# ShiftRegister.net
KiCad netlist of a schematic drawn in Altium Designer
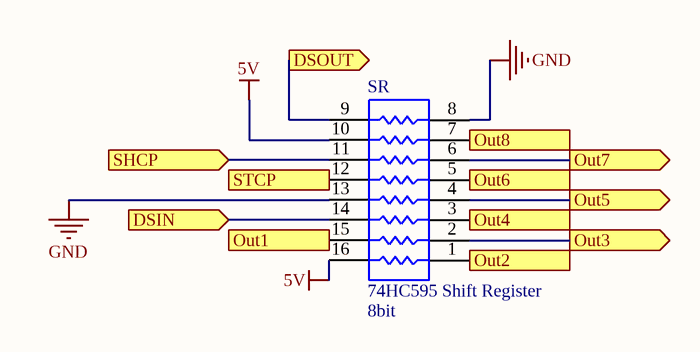
[diagram p0: ShiftRegister.SchDoc]

(export (version "E")
  (design (tool "Eeschema 10.0.6"))
  (components
    (comp (ref "SR")
      (value "74HC595 Shift Register")
      (footprint "SO-16_L")
      (description "Isolated Resistor Network")
      (fields (field (name "ALTIUM_VALUE") "8bit") (field (name "PUBLISHER") "Altium Limited"))
      (libsource (lib "Miscellaneous Devices") (part "Res Pack3"))
    )
  )
  (nets
    (net (code "1") (name "/DSIN") (class "Default")
      (node (ref "SR") (pin "14") (pinfunction "14_14") (pintype "passive"))
    )
    (net (code "2") (name "/DSOUT") (class "Default")
      (node (ref "SR") (pin "9") (pinfunction "9_9") (pintype "passive"))
    )
    (net (code "3") (name "/Out1") (class "Default")
      (node (ref "SR") (pin "15") (pinfunction "15_15") (pintype "passive"))
    )
    (net (code "4") (name "/Out2") (class "Default")
      (node (ref "SR") (pin "1") (pinfunction "1_1") (pintype "passive"))
    )
    (net (code "5") (name "/Out3") (class "Default")
      (node (ref "SR") (pin "2") (pinfunction "2_2") (pintype "passive"))
    )
    (net (code "6") (name "/Out4") (class "Default")
      (node (ref "SR") (pin "3") (pinfunction "3_3") (pintype "passive"))
    )
    (net (code "7") (name "/Out5") (class "Default")
      (node (ref "SR") (pin "4") (pinfunction "4_4") (pintype "passive"))
    )
    (net (code "8") (name "/Out6") (class "Default")
      (node (ref "SR") (pin "5") (pinfunction "5_5") (pintype "passive"))
    )
    (net (code "9") (name "/Out7") (class "Default")
      (node (ref "SR") (pin "6") (pinfunction "6_6") (pintype "passive"))
    )
    (net (code "10") (name "/Out8") (class "Default")
      (node (ref "SR") (pin "7") (pinfunction "7_7") (pintype "passive"))
    )
    (net (code "11") (name "/SHCP") (class "Default")
      (node (ref "SR") (pin "11") (pinfunction "11_11") (pintype "passive"))
    )
    (net (code "12") (name "/STCP") (class "Default")
      (node (ref "SR") (pin "12") (pinfunction "12_12") (pintype "passive"))
    )
    (net (code "13") (name "5V") (class "Default")
      (node (ref "SR") (pin "10") (pinfunction "10_10") (pintype "passive"))
      (node (ref "SR") (pin "16") (pinfunction "16_16") (pintype "passive"))
    )
    (net (code "14") (name "GND") (class "Default")
      (node (ref "SR") (pin "13") (pinfunction "13_13") (pintype "passive"))
      (node (ref "SR") (pin "8") (pinfunction "8_8") (pintype "passive"))
    )
  )
)
